# Kapitoshka.net
KiCad netlist of a schematic drawn in Altium Designer
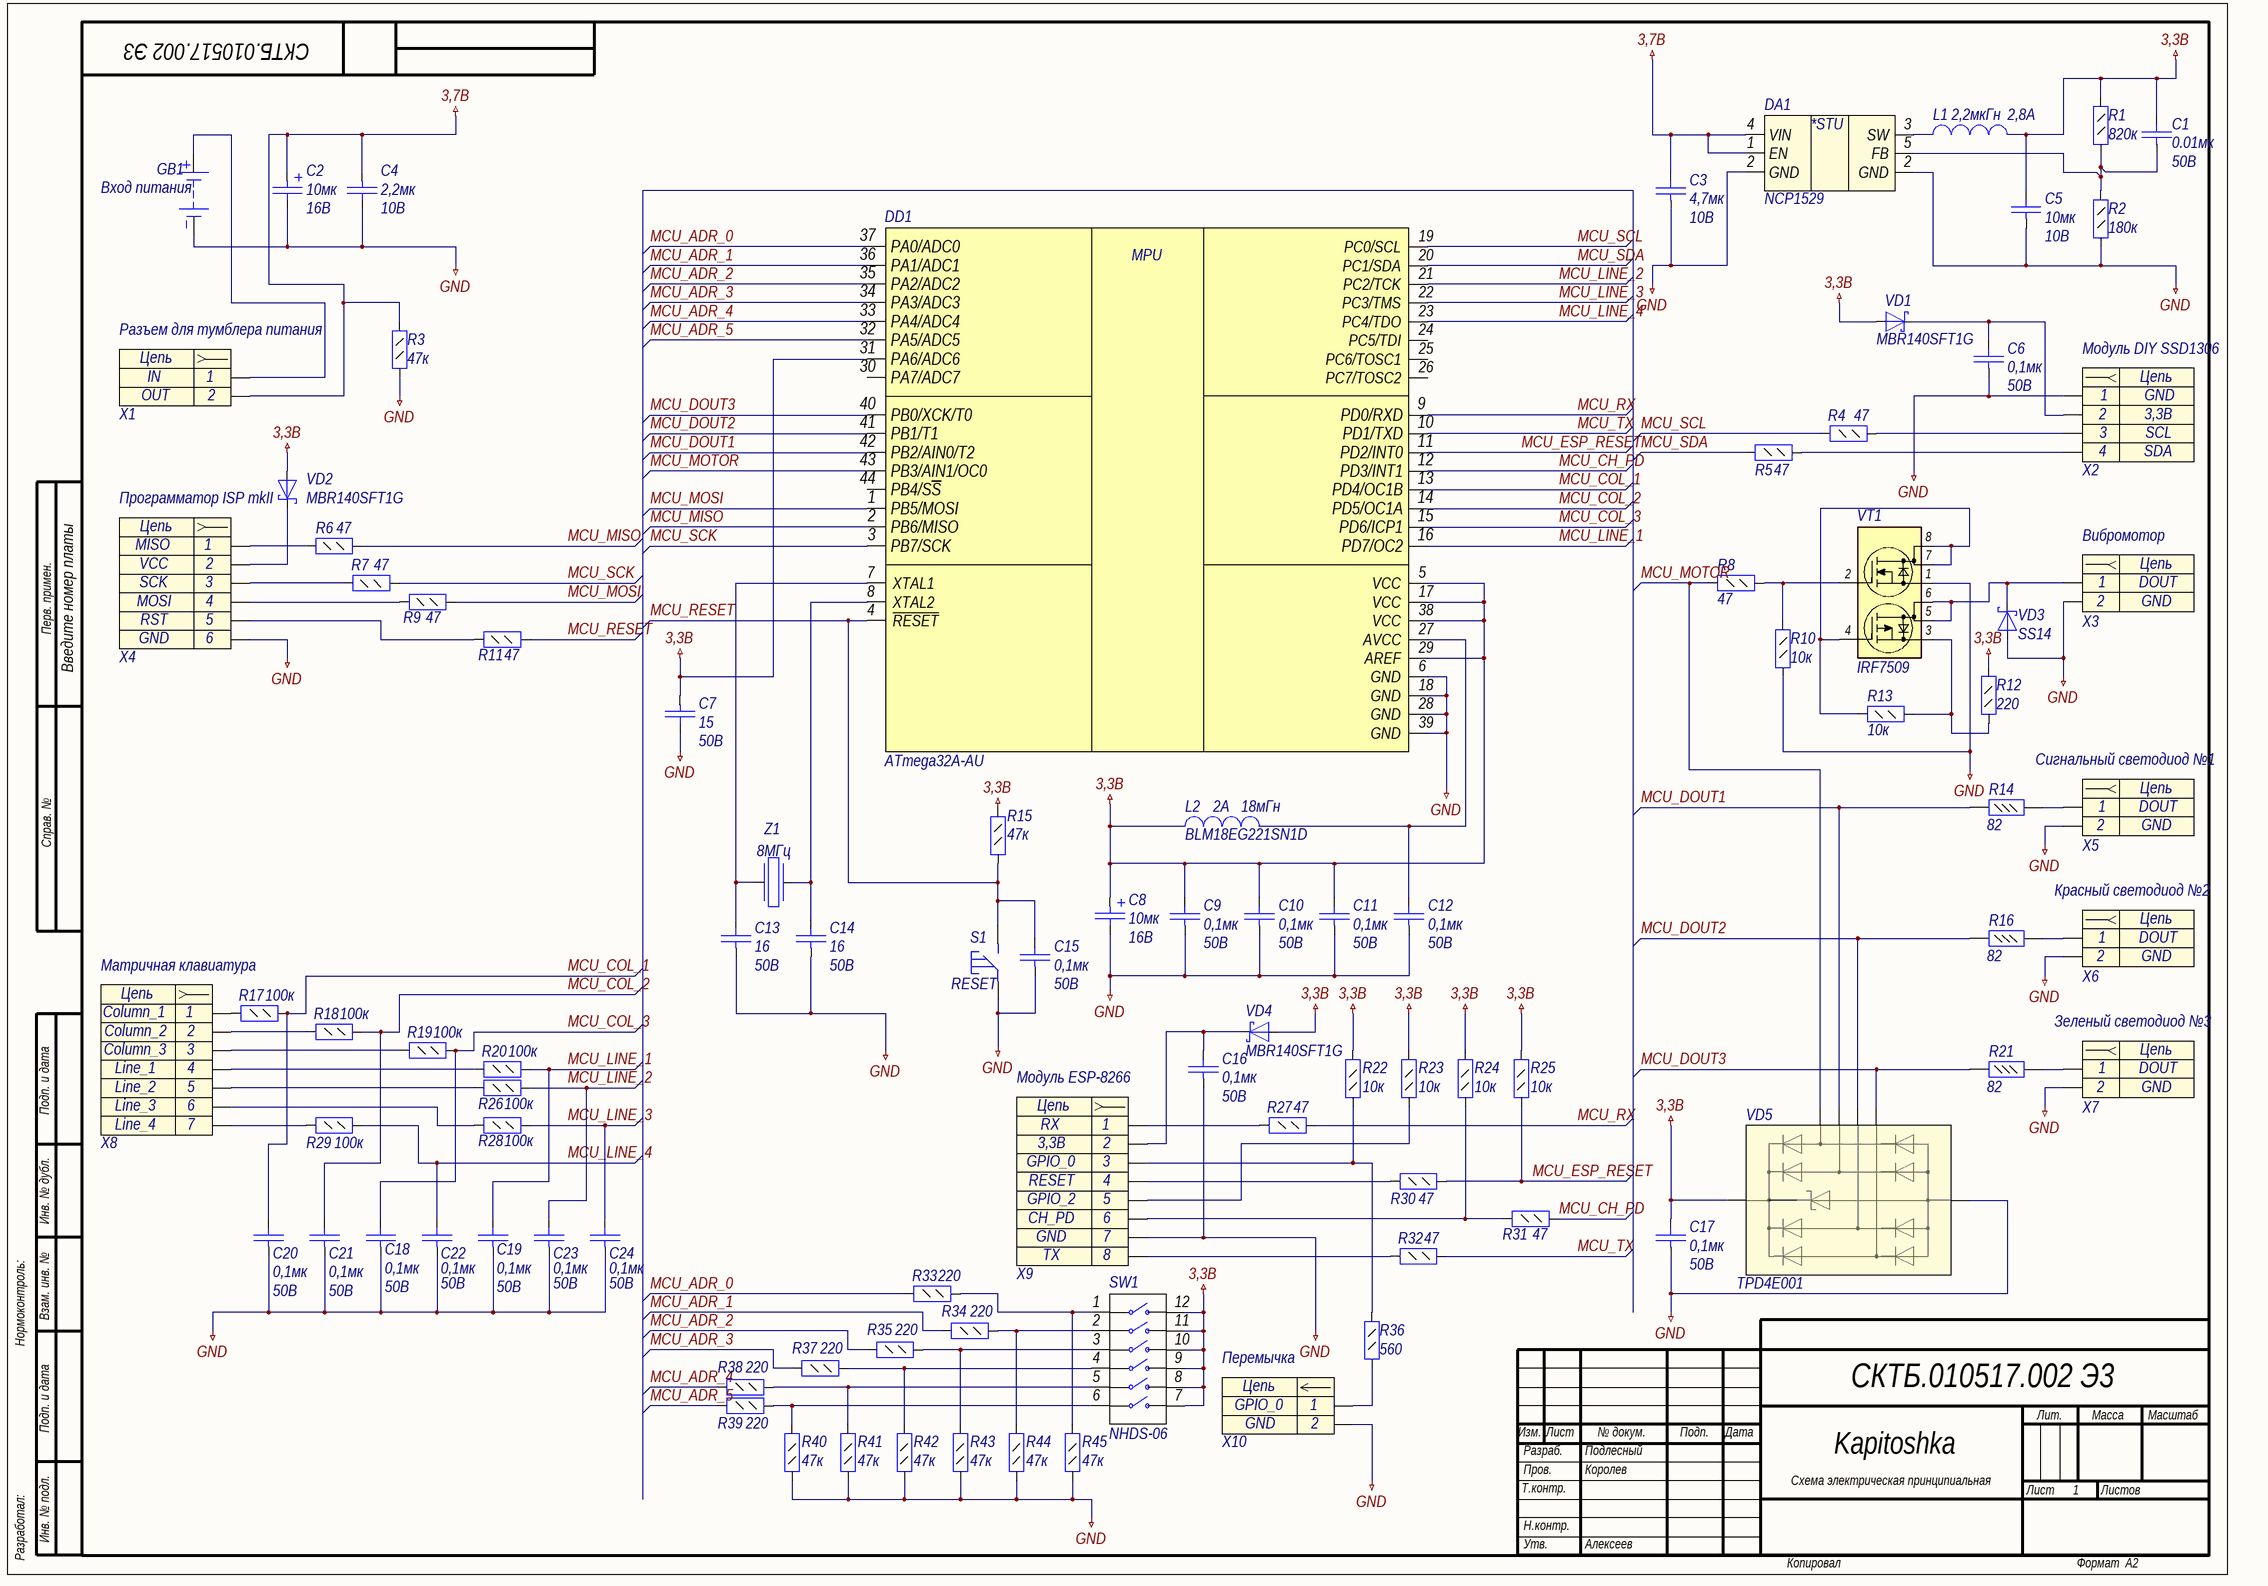
[diagram p0: Kapitoshka.SchDoc]

(export (version "E")
  (design (tool "Eeschema 10.0.6"))
  (components
    (comp (ref "C1")
      (value "0.01мк")
      (footprint "Kapitoshka:C0603")
      (description "Конденсатор")
      (fields (field (name "VOLTAGE") "50В"))
      (libsource (lib "Kapitoshka") (part "Capacitor"))
    )
    (comp (ref "C2")
      (value "10мк")
      (footprint "Kapitoshka:3216 Case-A")
      (description "Конденсатор полярный")
      (fields (field (name "VOLTAGE") "16В"))
      (libsource (lib "Kapitoshka") (part "Capacitor_pol"))
    )
    (comp (ref "C3")
      (value "4,7мк")
      (footprint "Kapitoshka:C0603")
      (description "Конденсатор")
      (fields (field (name "VOLTAGE") "10В"))
      (libsource (lib "Kapitoshka") (part "Capacitor"))
    )
    (comp (ref "C4")
      (value "2,2мк")
      (footprint "Kapitoshka:C0603")
      (description "Конденсатор")
      (fields (field (name "VOLTAGE") "10В"))
      (libsource (lib "Kapitoshka") (part "Capacitor"))
    )
    (comp (ref "C5")
      (value "10мк")
      (footprint "Kapitoshka:C0805")
      (description "Конденсатор")
      (fields (field (name "VOLTAGE") "10В"))
      (libsource (lib "Kapitoshka") (part "Capacitor"))
    )
    (comp (ref "C6")
      (value "0,1мк")
      (footprint "Kapitoshka:C0603")
      (description "Конденсатор")
      (fields (field (name "VOLTAGE") "50В"))
      (libsource (lib "Kapitoshka") (part "Capacitor"))
    )
    (comp (ref "C7")
      (value "15")
      (footprint "Kapitoshka:C0603")
      (description "Конденсатор")
      (fields (field (name "VOLTAGE") "50В"))
      (libsource (lib "Kapitoshka") (part "Capacitor"))
    )
    (comp (ref "C8")
      (value "10мк")
      (footprint "Kapitoshka:3216 Case-A")
      (description "Конденсатор полярный")
      (fields (field (name "VOLTAGE") "16В"))
      (libsource (lib "Kapitoshka") (part "Capacitor_pol"))
    )
    (comp (ref "C9")
      (value "0,1мк")
      (footprint "Kapitoshka:C0603")
      (description "Конденсатор")
      (fields (field (name "VOLTAGE") "50В"))
      (libsource (lib "Kapitoshka") (part "Capacitor"))
    )
    (comp (ref "C10")
      (value "0,1мк")
      (footprint "Kapitoshka:C0603")
      (description "Конденсатор")
      (fields (field (name "VOLTAGE") "50В"))
      (libsource (lib "Kapitoshka") (part "Capacitor"))
    )
    (comp (ref "C11")
      (value "0,1мк")
      (footprint "Kapitoshka:C0603")
      (description "Конденсатор")
      (fields (field (name "VOLTAGE") "50В"))
      (libsource (lib "Kapitoshka") (part "Capacitor"))
    )
    (comp (ref "C12")
      (value "0,1мк")
      (footprint "Kapitoshka:C0603")
      (description "Конденсатор")
      (fields (field (name "VOLTAGE") "50В"))
      (libsource (lib "Kapitoshka") (part "Capacitor"))
    )
    (comp (ref "C13")
      (value "16")
      (footprint "Kapitoshka:C0805")
      (description "Конденсатор")
      (fields (field (name "VOLTAGE") "50В"))
      (libsource (lib "Kapitoshka") (part "Capacitor"))
    )
    (comp (ref "C14")
      (value "16")
      (footprint "Kapitoshka:C0805")
      (description "Конденсатор")
      (fields (field (name "VOLTAGE") "50В"))
      (libsource (lib "Kapitoshka") (part "Capacitor"))
    )
    (comp (ref "C15")
      (value "0,1мк")
      (footprint "Kapitoshka:C0603")
      (description "Конденсатор")
      (fields (field (name "VOLTAGE") "50В"))
      (libsource (lib "Kapitoshka") (part "Capacitor"))
    )
    (comp (ref "C16")
      (value "0,1мк")
      (footprint "Kapitoshka:C0603")
      (description "Конденсатор")
      (fields (field (name "VOLTAGE") "50В"))
      (libsource (lib "Kapitoshka") (part "Capacitor"))
    )
    (comp (ref "C17")
      (value "0,1мк")
      (footprint "Kapitoshka:C0603")
      (description "Конденсатор")
      (fields (field (name "VOLTAGE") "50В"))
      (libsource (lib "Kapitoshka") (part "Capacitor"))
    )
    (comp (ref "C18")
      (value "0,1мк")
      (footprint "Kapitoshka:C0603")
      (description "Конденсатор")
      (fields (field (name "VOLTAGE") "50В"))
      (libsource (lib "Kapitoshka") (part "Capacitor"))
    )
    (comp (ref "C19")
      (value "0,1мк")
      (footprint "Kapitoshka:C0603")
      (description "Конденсатор")
      (fields (field (name "VOLTAGE") "50В"))
      (libsource (lib "Kapitoshka") (part "Capacitor"))
    )
    (comp (ref "C20")
      (value "0,1мк")
      (footprint "Kapitoshka:C0603")
      (description "Конденсатор")
      (fields (field (name "VOLTAGE") "50В"))
      (libsource (lib "Kapitoshka") (part "Capacitor"))
    )
    (comp (ref "C21")
      (value "0,1мк")
      (footprint "Kapitoshka:C0603")
      (description "Конденсатор")
      (fields (field (name "VOLTAGE") "50В"))
      (libsource (lib "Kapitoshka") (part "Capacitor"))
    )
    (comp (ref "C22")
      (value "0,1мк")
      (footprint "Kapitoshka:C0603")
      (description "Конденсатор")
      (fields (field (name "VOLTAGE") "50В"))
      (libsource (lib "Kapitoshka") (part "Capacitor"))
    )
    (comp (ref "C23")
      (value "0,1мк")
      (footprint "Kapitoshka:C0603")
      (description "Конденсатор")
      (fields (field (name "VOLTAGE") "50В"))
      (libsource (lib "Kapitoshka") (part "Capacitor"))
    )
    (comp (ref "C24")
      (value "0,1мк")
      (footprint "Kapitoshka:C0603")
      (description "Конденсатор")
      (fields (field (name "VOLTAGE") "50В"))
      (libsource (lib "Kapitoshka") (part "Capacitor"))
    )
    (comp (ref "DA1")
      (value "NCP1529")
      (footprint "Kapitoshka:TSOP-5")
      (description "Output Voltage Step-down  Converter")
      (libsource (lib "Kapitoshka") (part "NCP1529"))
    )
    (comp (ref "DD1")
      (value "ATmega32A-AU")
      (footprint "Kapitoshka:TQFP-44")
      (description "Микроконтроллер 44-pin")
      (fields (field (name "NAME") "ATmega32A-AU"))
      (libsource (lib "Kapitoshka") (part "ATmega32A-AU"))
    )
    (comp (ref "GB1")
      (value "Вход питания")
      (footprint "Kapitoshka:KLS5-818-D")
      (libsource (lib "Kapitoshka") (part "Battery compartment"))
    )
    (comp (ref "L1")
      (value "2,2мкГн")
      (footprint "Kapitoshka:SDR0604")
      (description "Катушка индуктивности")
      (fields (field (name "IMAX") "2,8А"))
      (libsource (lib "Kapitoshka") (part "Inductor"))
    )
    (comp (ref "L2")
      (value "18мГн")
      (footprint "Kapitoshka:L0603")
      (description "Катушка индуктивности")
      (fields (field (name "NAME") "BLM18EG221SN1D") (field (name "IMAX") "2А"))
      (libsource (lib "Kapitoshka") (part "Inductor"))
    )
    (comp (ref "R1")
      (value "820к")
      (footprint "Kapitoshka:R0603")
      (description "0.125Вт 0805 47 Ом, 1%, Чип резистор (SMD)")
      (libsource (lib "") (part "Resistor_0,125Вт_2"))
    )
    (comp (ref "R2")
      (value "180к")
      (footprint "Kapitoshka:R0603")
      (description "0.125Вт 0805 47 Ом, 1%, Чип резистор (SMD)")
      (libsource (lib "") (part "Resistor_0,125Вт_2"))
    )
    (comp (ref "R3")
      (value "47к")
      (footprint "Kapitoshka:R0603")
      (description "Резистор")
      (libsource (lib "") (part "Resistor_0,125Вт_2"))
    )
    (comp (ref "R4")
      (value "47")
      (footprint "Kapitoshka:R0603")
      (description "0.125Вт 0805 47 Ом, 1%, Чип резистор (SMD)")
      (libsource (lib "Stove_Light") (part "Resistor_0,125Вт"))
    )
    (comp (ref "R5")
      (value "47")
      (footprint "Kapitoshka:R0603")
      (description "0.125Вт 0805 47 Ом, 1%, Чип резистор (SMD)")
      (libsource (lib "Stove_Light") (part "Resistor_0,125Вт"))
    )
    (comp (ref "R6")
      (value "47")
      (footprint "Kapitoshka:R0603")
      (description "Резистор")
      (libsource (lib "") (part "Resistor_0,125Вт_1"))
    )
    (comp (ref "R7")
      (value "47")
      (footprint "Kapitoshka:R0603")
      (description "Резистор")
      (libsource (lib "") (part "Resistor_0,125Вт_1"))
    )
    (comp (ref "R8")
      (value "47")
      (footprint "Kapitoshka:R0603")
      (description "0.125Вт 0805 47 Ом, 1%, Чип резистор (SMD)")
      (libsource (lib "Stove_Light") (part "Resistor_0,125Вт"))
    )
    (comp (ref "R9")
      (value "47")
      (footprint "Kapitoshka:R0603")
      (description "Резистор")
      (libsource (lib "") (part "Resistor_0,125Вт_1"))
    )
    (comp (ref "R10")
      (value "10к")
      (footprint "Kapitoshka:R0603")
      (description "0.125Вт 0805 47 Ом, 1%, Чип резистор (SMD)")
      (libsource (lib "") (part "Resistor_0,125Вт_2"))
    )
    (comp (ref "R11")
      (value "47")
      (footprint "Kapitoshka:R0603")
      (description "Резистор")
      (libsource (lib "") (part "Resistor_0,125Вт_1"))
    )
    (comp (ref "R12")
      (value "220")
      (footprint "Kapitoshka:R0603")
      (description "0.125Вт 0805 47 Ом, 1%, Чип резистор (SMD)")
      (libsource (lib "") (part "Resistor_0,125Вт_3"))
    )
    (comp (ref "R13")
      (value "10к")
      (footprint "Kapitoshka:R0603")
      (description "0.125Вт 0805 10 кОм, 1%, Чип резистор (SMD)")
      (libsource (lib "") (part "Resistor_0,125Вт_1"))
    )
    (comp (ref "R14")
      (value "82")
      (footprint "Kapitoshka:R0603")
      (description "Резистор")
      (libsource (lib "Kapitoshka") (part "Resistor_0,05Вт"))
    )
    (comp (ref "R15")
      (value "47к")
      (footprint "Kapitoshka:R0603")
      (description "Резистор")
      (libsource (lib "") (part "Resistor_0,125Вт_2"))
    )
    (comp (ref "R16")
      (value "82")
      (footprint "Kapitoshka:R0603")
      (description "Резистор")
      (libsource (lib "Kapitoshka") (part "Resistor_0,05Вт"))
    )
    (comp (ref "R17")
      (value "100к")
      (footprint "Kapitoshka:R0603")
      (description "0.125Вт 0805 47 Ом, 1%, Чип резистор (SMD)")
      (libsource (lib "Stove_Light") (part "Resistor_0,125Вт"))
    )
    (comp (ref "R18")
      (value "100к")
      (footprint "Kapitoshka:R0603")
      (description "0.125Вт 0805 47 Ом, 1%, Чип резистор (SMD)")
      (libsource (lib "Stove_Light") (part "Resistor_0,125Вт"))
    )
    (comp (ref "R19")
      (value "100к")
      (footprint "Kapitoshka:R0603")
      (description "0.125Вт 0805 47 Ом, 1%, Чип резистор (SMD)")
      (libsource (lib "Stove_Light") (part "Resistor_0,125Вт"))
    )
    (comp (ref "R20")
      (value "100к")
      (footprint "Kapitoshka:R0603")
      (description "0.125Вт 0805 47 Ом, 1%, Чип резистор (SMD)")
      (libsource (lib "Stove_Light") (part "Resistor_0,125Вт"))
    )
    (comp (ref "R21")
      (value "82")
      (footprint "Kapitoshka:R0603")
      (description "Резистор")
      (libsource (lib "Kapitoshka") (part "Resistor_0,05Вт"))
    )
    (comp (ref "R22")
      (value "10к")
      (footprint "Kapitoshka:R0603")
      (description "Резистор")
      (libsource (lib "Kapitoshka") (part "Resistor_0,125Вт"))
    )
    (comp (ref "R23")
      (value "10к")
      (footprint "Kapitoshka:R0603")
      (description "Резистор")
      (libsource (lib "Kapitoshka") (part "Resistor_0,125Вт"))
    )
    (comp (ref "R24")
      (value "10к")
      (footprint "Kapitoshka:R0603")
      (description "Резистор")
      (libsource (lib "Kapitoshka") (part "Resistor_0,125Вт"))
    )
    (comp (ref "R25")
      (value "10к")
      (footprint "Kapitoshka:R0603")
      (description "Резистор")
      (libsource (lib "Kapitoshka") (part "Resistor_0,125Вт"))
    )
    (comp (ref "R26")
      (value "100к")
      (footprint "Kapitoshka:R0603")
      (description "0.125Вт 0805 47 Ом, 1%, Чип резистор (SMD)")
      (libsource (lib "Stove_Light") (part "Resistor_0,125Вт"))
    )
    (comp (ref "R27")
      (value "47")
      (footprint "Kapitoshka:R0603")
      (description "0.125Вт 0805 47 Ом, 1%, Чип резистор (SMD)")
      (libsource (lib "Stove_Light") (part "Resistor_0,125Вт"))
    )
    (comp (ref "R28")
      (value "100к")
      (footprint "Kapitoshka:R0603")
      (description "0.125Вт 0805 47 Ом, 1%, Чип резистор (SMD)")
      (libsource (lib "Stove_Light") (part "Resistor_0,125Вт"))
    )
    (comp (ref "R29")
      (value "100к")
      (footprint "Kapitoshka:R0603")
      (description "0.125Вт 0805 47 Ом, 1%, Чип резистор (SMD)")
      (libsource (lib "Stove_Light") (part "Resistor_0,125Вт"))
    )
    (comp (ref "R30")
      (value "47")
      (footprint "Kapitoshka:R0603")
      (description "0.125Вт 0805 47 Ом, 1%, Чип резистор (SMD)")
      (libsource (lib "Stove_Light") (part "Resistor_0,125Вт"))
    )
    (comp (ref "R31")
      (value "47")
      (footprint "Kapitoshka:R0603")
      (description "0.125Вт 0805 47 Ом, 1%, Чип резистор (SMD)")
      (libsource (lib "Stove_Light") (part "Resistor_0,125Вт"))
    )
    (comp (ref "R32")
      (value "47")
      (footprint "Kapitoshka:R0603")
      (description "0.125Вт 0805 47 Ом, 1%, Чип резистор (SMD)")
      (libsource (lib "Stove_Light") (part "Resistor_0,125Вт"))
    )
    (comp (ref "R33")
      (value "220")
      (footprint "Kapitoshka:R0603")
      (description "0.125Вт 0805 47 Ом, 1%, Чип резистор (SMD)")
      (libsource (lib "Stove_Light") (part "Resistor_0,125Вт"))
    )
    (comp (ref "R34")
      (value "220")
      (footprint "Kapitoshka:R0603")
      (description "0.125Вт 0805 47 Ом, 1%, Чип резистор (SMD)")
      (libsource (lib "Stove_Light") (part "Resistor_0,125Вт"))
    )
    (comp (ref "R35")
      (value "220")
      (footprint "Kapitoshka:R0603")
      (description "0.125Вт 0805 47 Ом, 1%, Чип резистор (SMD)")
      (libsource (lib "Stove_Light") (part "Resistor_0,125Вт"))
    )
    (comp (ref "R36")
      (value "560")
      (footprint "Kapitoshka:R0603")
      (description "0.125Вт 0805 47 Ом, 1%, Чип резистор (SMD)")
      (libsource (lib "") (part "Resistor_0,125Вт_2"))
    )
    (comp (ref "R37")
      (value "220")
      (footprint "Kapitoshka:R0603")
      (description "0.125Вт 0805 47 Ом, 1%, Чип резистор (SMD)")
      (libsource (lib "Stove_Light") (part "Resistor_0,125Вт"))
    )
    (comp (ref "R38")
      (value "220")
      (footprint "Kapitoshka:R0603")
      (description "0.125Вт 0805 47 Ом, 1%, Чип резистор (SMD)")
      (libsource (lib "Stove_Light") (part "Resistor_0,125Вт"))
    )
    (comp (ref "R39")
      (value "220")
      (footprint "Kapitoshka:R0603")
      (description "0.125Вт 0805 47 Ом, 1%, Чип резистор (SMD)")
      (libsource (lib "Stove_Light") (part "Resistor_0,125Вт"))
    )
    (comp (ref "R40")
      (value "47к")
      (footprint "Kapitoshka:R0603")
      (description "Резистор")
      (libsource (lib "Kapitoshka") (part "Resistor_0,125Вт"))
    )
    (comp (ref "R41")
      (value "47к")
      (footprint "Kapitoshka:R0603")
      (description "Резистор")
      (libsource (lib "Kapitoshka") (part "Resistor_0,125Вт"))
    )
    (comp (ref "R42")
      (value "47к")
      (footprint "Kapitoshka:R0603")
      (description "Резистор")
      (libsource (lib "Kapitoshka") (part "Resistor_0,125Вт"))
    )
    (comp (ref "R43")
      (value "47к")
      (footprint "Kapitoshka:R0603")
      (description "Резистор")
      (libsource (lib "Kapitoshka") (part "Resistor_0,125Вт"))
    )
    (comp (ref "R44")
      (value "47к")
      (footprint "Kapitoshka:R0603")
      (description "Резистор")
      (libsource (lib "Kapitoshka") (part "Resistor_0,125Вт"))
    )
    (comp (ref "R45")
      (value "47к")
      (footprint "Kapitoshka:R0603")
      (description "Резистор")
      (libsource (lib "Kapitoshka") (part "Resistor_0,125Вт"))
    )
    (comp (ref "S1")
      (value "RESET")
      (footprint "Kapitoshka:DTSM 32")
      (description "Кнопка")
      (fields (field (name "NAME") "RESET"))
      (libsource (lib "Kapitoshka") (part "Button_SMD"))
    )
    (comp (ref "SW1")
      (value "NHDS-06")
      (footprint "Kapitoshka:NHDS-06")
      (description "DIP переключатель")
      (libsource (lib "Kapitoshka") (part "DS1040-06"))
    )
    (comp (ref "VD1")
      (value "MBR140SFT1G")
      (footprint "Kapitoshka:SMA")
      (description "Диод Шоттки")
      (libsource (lib "Kapitoshka") (part "DiodeSchottky"))
    )
    (comp (ref "VD2")
      (value "MBR140SFT1G")
      (footprint "Kapitoshka:SMA")
      (description "Диод Шоттки")
      (libsource (lib "Kapitoshka") (part "DiodeSchottky"))
    )
    (comp (ref "VD3")
      (value "SS14")
      (footprint "Kapitoshka:SMA")
      (description "Диод Шоттки")
      (libsource (lib "Kapitoshka") (part "DiodeSchottky"))
    )
    (comp (ref "VD4")
      (value "MBR140SFT1G")
      (footprint "Kapitoshka:SMA")
      (description "Диод Шоттки")
      (libsource (lib "Kapitoshka") (part "DiodeSchottky"))
    )
    (comp (ref "VD5")
      (value "TPD4E001")
      (footprint "Kapitoshka:SOT23-6")
      (description "Диодная сборка")
      (fields (field (name "MANUFACTURER") "Texas Instruments"))
      (libsource (lib "Kapitoshka") (part "TPD4E001"))
    )
    (comp (ref "VT1")
      (value "IRF7509")
      (footprint "Kapitoshka:Micro8")
      (description "Комплементарная сборка МОП")
      (fields (field (name "NAME") "IRF7509"))
      (libsource (lib "Kapitoshka") (part "IRF7509"))
    )
    (comp (ref "X1")
      (value "Разъем для тумблера питания")
      (footprint "Kapitoshka:2HOLE")
      (description "Разъем - 2 конт. розетка")
      (libsource (lib "Kapitoshka") (part "Header_2_sct"))
    )
    (comp (ref "X2")
      (value "Модуль DIY SSD1306")
      (footprint "Kapitoshka:OLED SSD1306")
      (description "Разъем - 4 конт. розетка")
      (libsource (lib "Kapitoshka") (part "Header_4_sct"))
    )
    (comp (ref "X3")
      (value "Вибромотор")
      (footprint "Kapitoshka:2HOLE")
      (description "Разъем - 2 конт. розетка")
      (libsource (lib "") (part "Header_2_sct_1"))
    )
    (comp (ref "X4")
      (value "Программатор ISP mkII")
      (footprint "Kapitoshka:PLS2-6")
      (description "Разъем - 5 конт. розетка")
      (libsource (lib "Kapitoshka") (part "Header_6_sct"))
    )
    (comp (ref "X5")
      (value "Сигнальный светодиод №1")
      (footprint "Kapitoshka:2HOLE")
      (description "Разъем - 2 конт. розетка")
      (libsource (lib "") (part "Header_2_sct_1"))
    )
    (comp (ref "X6")
      (value "Красный светодиод №2")
      (footprint "Kapitoshka:2HOLE")
      (description "Разъем - 2 конт. розетка")
      (libsource (lib "") (part "Header_2_sct_1"))
    )
    (comp (ref "X7")
      (value "Зеленый светодиод №3")
      (footprint "Kapitoshka:2HOLE")
      (description "Разъем - 2 конт. розетка")
      (libsource (lib "") (part "Header_2_sct_1"))
    )
    (comp (ref "X8")
      (value "Матричная клавиатура")
      (footprint "Kapitoshka:7HOLE")
      (description "Разъем - 5 конт. розетка")
      (libsource (lib "Kapitoshka") (part "Header_7_sct_"))
    )
    (comp (ref "X9")
      (value "Модуль ESP-8266")
      (footprint "Kapitoshka:ESP8266")
      (description "Разъем - 5 конт. розетка")
      (libsource (lib "Kapitoshka") (part "Header_8_sct"))
    )
    (comp (ref "X10")
      (value "Перемычка")
      (footprint "Kapitoshka:PLS2-2")
      (description "Разъем - 2 конт. вилка")
      (libsource (lib "Kapitoshka") (part "Header_2_plg"))
    )
    (comp (ref "Z1")
      (value "8МГц")
      (footprint "Kapitoshka:QSMD3.2x5")
      (description "Кварцевый резонатор")
      (libsource (lib "Kapitoshka") (part "Crystal"))
    )
  )
  (nets
    (net (code "1") (name "/MCU_ADR_0") (class "Default")
      (node (ref "DD1") (pin "37") (pinfunction "PA0/ADC0_37") (pintype "passive"))
      (node (ref "R33") (pin "2") (pinfunction "5_2") (pintype "passive"))
    )
    (net (code "2") (name "/MCU_ADR_1") (class "Default")
      (node (ref "DD1") (pin "36") (pinfunction "PA1/ADC1_36") (pintype "passive"))
      (node (ref "R34") (pin "2") (pinfunction "5_2") (pintype "passive"))
    )
    (net (code "3") (name "/MCU_ADR_2") (class "Default")
      (node (ref "DD1") (pin "35") (pinfunction "PA2/ADC2_35") (pintype "passive"))
      (node (ref "R35") (pin "2") (pinfunction "5_2") (pintype "passive"))
    )
    (net (code "4") (name "/MCU_ADR_3") (class "Default")
      (node (ref "DD1") (pin "34") (pinfunction "PA3/ADC3_34") (pintype "passive"))
      (node (ref "R37") (pin "2") (pinfunction "5_2") (pintype "passive"))
    )
    (net (code "5") (name "/MCU_ADR_4") (class "Default")
      (node (ref "DD1") (pin "33") (pinfunction "PA4/ADC4_33") (pintype "passive"))
      (node (ref "R38") (pin "2") (pinfunction "5_2") (pintype "passive"))
    )
    (net (code "6") (name "/MCU_ADR_5") (class "Default")
      (node (ref "DD1") (pin "32") (pinfunction "PA5/ADC5_32") (pintype "passive"))
      (node (ref "R39") (pin "2") (pinfunction "5_2") (pintype "passive"))
    )
    (net (code "7") (name "/MCU_CH_PD") (class "Default")
      (node (ref "DD1") (pin "12") (pinfunction "PD3/INT1_12") (pintype "passive"))
      (node (ref "R31") (pin "1") (pinfunction "1_1") (pintype "passive"))
    )
    (net (code "8") (name "/MCU_COL_1") (class "Default")
      (node (ref "C20") (pin "2") (pinfunction "2_2") (pintype "passive"))
      (node (ref "DD1") (pin "13") (pinfunction "PD4/OC1B_13") (pintype "passive"))
      (node (ref "R17") (pin "1") (pinfunction "1_1") (pintype "passive"))
    )
    (net (code "9") (name "/MCU_COL_2") (class "Default")
      (node (ref "C21") (pin "2") (pinfunction "2_2") (pintype "passive"))
      (node (ref "DD1") (pin "14") (pinfunction "PD5/OC1A_14") (pintype "passive"))
      (node (ref "R18") (pin "1") (pinfunction "1_1") (pintype "passive"))
    )
    (net (code "10") (name "/MCU_COL_3") (class "Default")
      (node (ref "C18") (pin "2") (pinfunction "2_2") (pintype "passive"))
      (node (ref "DD1") (pin "15") (pinfunction "PD6/ICP1_15") (pintype "passive"))
      (node (ref "R19") (pin "1") (pinfunction "1_1") (pintype "passive"))
    )
    (net (code "11") (name "/MCU_DOUT1") (class "Default")
      (node (ref "DD1") (pin "42") (pinfunction "PB2/AIN0/T2_42") (pintype "passive"))
      (node (ref "R14") (pin "1") (pinfunction "1_1") (pintype "passive"))
      (node (ref "VD5") (pin "3") (pinfunction "IO2_3") (pintype "passive"))
    )
    (net (code "12") (name "/MCU_DOUT2") (class "Default")
      (node (ref "DD1") (pin "41") (pinfunction "PB1/T1_41") (pintype "passive"))
      (node (ref "R16") (pin "1") (pinfunction "1_1") (pintype "passive"))
      (node (ref "VD5") (pin "4") (pinfunction "IO3_4") (pintype "passive"))
    )
    (net (code "13") (name "/MCU_DOUT3") (class "Default")
      (node (ref "DD1") (pin "40") (pinfunction "PB0/XCK/T0_40") (pintype "passive"))
      (node (ref "R21") (pin "1") (pinfunction "1_1") (pintype "passive"))
      (node (ref "VD5") (pin "6") (pinfunction "IO4_6") (pintype "passive"))
    )
    (net (code "14") (name "/MCU_ESP_RESET") (class "Default")
      (node (ref "DD1") (pin "11") (pinfunction "PD2/INT0_11") (pintype "passive"))
      (node (ref "R25") (pin "1") (pinfunction "1_1") (pintype "passive"))
      (node (ref "R30") (pin "1") (pinfunction "1_1") (pintype "passive"))
    )
    (net (code "15") (name "/MCU_LINE_1") (class "Default")
      (node (ref "C19") (pin "2") (pinfunction "2_2") (pintype "passive"))
      (node (ref "DD1") (pin "16") (pinfunction "PD7/OC2_16") (pintype "passive"))
      (node (ref "R20") (pin "1") (pinfunction "1_1") (pintype "passive"))
    )
    (net (code "16") (name "/MCU_LINE_2") (class "Default")
      (node (ref "C23") (pin "2") (pinfunction "2_2") (pintype "passive"))
      (node (ref "DD1") (pin "21") (pinfunction "PC2/TCK_21") (pintype "passive"))
      (node (ref "R26") (pin "1") (pinfunction "1_1") (pintype "passive"))
    )
    (net (code "17") (name "/MCU_LINE_3") (class "Default")
      (node (ref "C24") (pin "2") (pinfunction "2_2") (pintype "passive"))
      (node (ref "DD1") (pin "22") (pinfunction "PC3/TMS_22") (pintype "passive"))
      (node (ref "R28") (pin "1") (pinfunction "1_1") (pintype "passive"))
    )
    (net (code "18") (name "/MCU_LINE_4") (class "Default")
      (node (ref "C22") (pin "2") (pinfunction "2_2") (pintype "passive"))
      (node (ref "DD1") (pin "23") (pinfunction "PC4/TDO_23") (pintype "passive"))
      (node (ref "R29") (pin "1") (pinfunction "1_1") (pintype "passive"))
    )
    (net (code "19") (name "/MCU_MISO") (class "Default")
      (node (ref "DD1") (pin "2") (pinfunction "PB6/MISO_2") (pintype "passive"))
      (node (ref "R6") (pin "2") (pinfunction "5_2") (pintype "passive"))
    )
    (net (code "20") (name "/MCU_MOSI") (class "Default")
      (node (ref "DD1") (pin "1") (pinfunction "PB5/MOSI_1") (pintype "passive"))
      (node (ref "R9") (pin "2") (pinfunction "5_2") (pintype "passive"))
    )
    (net (code "21") (name "/MCU_MOTOR") (class "Default")
      (node (ref "DD1") (pin "43") (pinfunction "PB3/AIN1/OC0_43") (pintype "passive"))
      (node (ref "R8") (pin "2") (pinfunction "5_2") (pintype "passive"))
      (node (ref "VD5") (pin "1") (pinfunction "IO1_1") (pintype "passive"))
    )
    (net (code "22") (name "/MCU_RESET") (class "Default")
      (node (ref "C15") (pin "2") (pinfunction "2_2") (pintype "passive"))
      (node (ref "DD1") (pin "4") (pinfunction "~{RESET}_4") (pintype "passive"))
      (node (ref "R11") (pin "2") (pinfunction "5_2") (pintype "passive"))
      (node (ref "R15") (pin "2") (pinfunction "5_2") (pintype "passive"))
      (node (ref "S1") (pin "3") (pinfunction "3_3") (pintype "passive"))
    )
    (net (code "23") (name "/MCU_RX") (class "Default")
      (node (ref "DD1") (pin "9") (pinfunction "PD0/RXD_9") (pintype "passive"))
      (node (ref "R27") (pin "1") (pinfunction "1_1") (pintype "passive"))
    )
    (net (code "24") (name "/MCU_SCK") (class "Default")
      (node (ref "DD1") (pin "3") (pinfunction "PB7/SCK_3") (pintype "passive"))
      (node (ref "R7") (pin "2") (pinfunction "5_2") (pintype "passive"))
    )
    (net (code "25") (name "/MCU_SCL") (class "Default")
      (node (ref "DD1") (pin "19") (pinfunction "PC0/SCL_19") (pintype "passive"))
      (node (ref "R4") (pin "2") (pinfunction "5_2") (pintype "passive"))
    )
    (net (code "26") (name "/MCU_SDA") (class "Default")
      (node (ref "DD1") (pin "20") (pinfunction "PC1/SDA_20") (pintype "passive"))
      (node (ref "R5") (pin "2") (pinfunction "5_2") (pintype "passive"))
    )
    (net (code "27") (name "/MCU_TX") (class "Default")
      (node (ref "DD1") (pin "10") (pinfunction "PD1/TXD_10") (pintype "passive"))
      (node (ref "R32") (pin "1") (pinfunction "1_1") (pintype "passive"))
    )
    (net (code "28") (name "3,3В") (class "Default")
      (node (ref "C1") (pin "2") (pinfunction "2_2") (pintype "passive"))
      (node (ref "C10") (pin "2") (pinfunction "2_2") (pintype "passive"))
      (node (ref "C11") (pin "2") (pinfunction "2_2") (pintype "passive"))
      (node (ref "C17") (pin "2") (pinfunction "2_2") (pintype "passive"))
      (node (ref "C5") (pin "2") (pinfunction "2_2") (pintype "passive"))
      (node (ref "C7") (pin "1") (pinfunction "1_1") (pintype "passive"))
      (node (ref "C8") (pin "1") (pinfunction "1_1") (pintype "passive"))
      (node (ref "C9") (pin "2") (pinfunction "2_2") (pintype "passive"))
      (node (ref "DD1") (pin "17") (pinfunction "VCC_17") (pintype "passive"))
      (node (ref "DD1") (pin "29") (pinfunction "AREF_29") (pintype "passive"))
      (node (ref "DD1") (pin "31") (pinfunction "PA6/ADC6_31") (pintype "passive"))
      (node (ref "DD1") (pin "38") (pinfunction "VCC_38") (pintype "passive"))
      (node (ref "DD1") (pin "5") (pinfunction "VCC_5") (pintype "passive"))
      (node (ref "L1") (pin "2") (pinfunction "2_2") (pintype "passive"))
      (node (ref "L2") (pin "1") (pinfunction "1_1") (pintype "passive"))
      (node (ref "R1") (pin "1") (pinfunction "1_1") (pintype "passive"))
      (node (ref "R12") (pin "2") (pinfunction "5_2") (pintype "passive"))
      (node (ref "R15") (pin "1") (pinfunction "1_1") (pintype "passive"))
      (node (ref "R22") (pin "2") (pinfunction "5_2") (pintype "passive"))
      (node (ref "R23") (pin "2") (pinfunction "5_2") (pintype "passive"))
      (node (ref "R24") (pin "2") (pinfunction "5_2") (pintype "passive"))
      (node (ref "R25") (pin "2") (pinfunction "5_2") (pintype "passive"))
      (node (ref "SW1") (pin "10") (pintype "passive"))
      (node (ref "SW1") (pin "11") (pintype "passive"))
      (node (ref "SW1") (pin "12") (pintype "passive"))
      (node (ref "SW1") (pin "7") (pintype "passive"))
      (node (ref "SW1") (pin "8") (pintype "passive"))
      (node (ref "SW1") (pin "9") (pintype "passive"))
      (node (ref "VD1") (pin "2") (pinfunction "A_2") (pintype "passive"))
      (node (ref "VD2") (pin "2") (pinfunction "A_2") (pintype "passive"))
      (node (ref "VD4") (pin "2") (pinfunction "A_2") (pintype "passive"))
      (node (ref "VD5") (pin "5") (pinfunction "VCC_5") (pintype "passive"))
    )
    (net (code "29") (name "3,7В") (class "Default")
      (node (ref "C2") (pin "1") (pinfunction "1_1") (pintype "passive"))
      (node (ref "C3") (pin "2") (pinfunction "2_2") (pintype "passive"))
      (node (ref "C4") (pin "1") (pinfunction "1_1") (pintype "passive"))
      (node (ref "DA1") (pin "1") (pinfunction "EN_1") (pintype "power_in"))
      (node (ref "DA1") (pin "4") (pinfunction "VIN_4") (pintype "power_in"))
      (node (ref "R3") (pin "1") (pinfunction "1_1") (pintype "passive"))
      (node (ref "X1") (pin "2") (pinfunction "2_2") (pintype "passive"))
    )
    (net (code "30") (name "GND") (class "Default")
      (node (ref "C10") (pin "1") (pinfunction "1_1") (pintype "passive"))
      (node (ref "C11") (pin "1") (pinfunction "1_1") (pintype "passive"))
      (node (ref "C12") (pin "1") (pinfunction "1_1") (pintype "passive"))
      (node (ref "C13") (pin "1") (pinfunction "1_1") (pintype "passive"))
      (node (ref "C14") (pin "1") (pinfunction "1_1") (pintype "passive"))
      (node (ref "C15") (pin "1") (pinfunction "1_1") (pintype "passive"))
      (node (ref "C16") (pin "1") (pinfunction "1_1") (pintype "passive"))
      (node (ref "C17") (pin "1") (pinfunction "1_1") (pintype "passive"))
      (node (ref "C18") (pin "1") (pinfunction "1_1") (pintype "passive"))
      (node (ref "C19") (pin "1") (pinfunction "1_1") (pintype "passive"))
      (node (ref "C2") (pin "2") (pinfunction "2_2") (pintype "passive"))
      (node (ref "C20") (pin "1") (pinfunction "1_1") (pintype "passive"))
      (node (ref "C21") (pin "1") (pinfunction "1_1") (pintype "passive"))
      (node (ref "C22") (pin "1") (pinfunction "1_1") (pintype "passive"))
      (node (ref "C23") (pin "1") (pinfunction "1_1") (pintype "passive"))
      (node (ref "C24") (pin "1") (pinfunction "1_1") (pintype "passive"))
      (node (ref "C3") (pin "1") (pinfunction "1_1") (pintype "passive"))
      (node (ref "C4") (pin "2") (pinfunction "2_2") (pintype "passive"))
      (node (ref "C5") (pin "1") (pinfunction "1_1") (pintype "passive"))
      (node (ref "C6") (pin "1") (pinfunction "1_1") (pintype "passive"))
      (node (ref "C7") (pin "2") (pinfunction "2_2") (pintype "passive"))
      (node (ref "C8") (pin "2") (pinfunction "2_2") (pintype "passive"))
      (node (ref "C9") (pin "1") (pinfunction "1_1") (pintype "passive"))
      (node (ref "DA1") (pin "2") (pinfunction "GND_2") (pintype "power_in"))
      (node (ref "DD1") (pin "18") (pinfunction "GND_18") (pintype "passive"))
      (node (ref "DD1") (pin "28") (pinfunction "GND_28") (pintype "passive"))
      (node (ref "DD1") (pin "39") (pinfunction "GND_39") (pintype "passive"))
      (node (ref "DD1") (pin "6") (pinfunction "GND_6") (pintype "passive"))
      (node (ref "GB1") (pin "2") (pinfunction "2_2") (pintype "passive"))
      (node (ref "R10") (pin "2") (pinfunction "5_2") (pintype "passive"))
      (node (ref "R2") (pin "2") (pinfunction "5_2") (pintype "passive"))
      (node (ref "R3") (pin "2") (pinfunction "5_2") (pintype "passive"))
      (node (ref "R40") (pin "1") (pinfunction "1_1") (pintype "passive"))
      (node (ref "R41") (pin "1") (pinfunction "1_1") (pintype "passive"))
      (node (ref "R42") (pin "1") (pinfunction "1_1") (pintype "passive"))
      (node (ref "R43") (pin "1") (pinfunction "1_1") (pintype "passive"))
      (node (ref "R44") (pin "1") (pinfunction "1_1") (pintype "passive"))
      (node (ref "R45") (pin "1") (pinfunction "1_1") (pintype "passive"))
      (node (ref "S1") (pin "1") (pinfunction "1_1") (pintype "passive"))
      (node (ref "VD3") (pin "2") (pinfunction "A_2") (pintype "passive"))
      (node (ref "VD5") (pin "2") (pinfunction "GND_2") (pintype "passive"))
      (node (ref "VT1") (pin "1") (pinfunction "S1_1") (pintype "passive"))
      (node (ref "X10") (pin "2") (pinfunction "2_2") (pintype "passive"))
      (node (ref "X2") (pin "1") (pinfunction "1_1") (pintype "passive"))
      (node (ref "X3") (pin "2") (pinfunction "2_2") (pintype "passive"))
      (node (ref "X4") (pin "6") (pinfunction "6_6") (pintype "passive"))
      (node (ref "X5") (pin "2") (pinfunction "2_2") (pintype "passive"))
      (node (ref "X6") (pin "2") (pinfunction "2_2") (pintype "passive"))
      (node (ref "X7") (pin "2") (pinfunction "2_2") (pintype "passive"))
      (node (ref "X9") (pin "7") (pinfunction "7_7") (pintype "passive"))
    )
    (net (code "31") (name "Net-(DA1-FB)") (class "Default")
      (node (ref "C1") (pin "1") (pinfunction "1_1") (pintype "passive"))
      (node (ref "DA1") (pin "5") (pinfunction "FB_5") (pintype "power_in"))
      (node (ref "R1") (pin "2") (pinfunction "5_2") (pintype "passive"))
      (node (ref "R2") (pin "1") (pinfunction "1_1") (pintype "passive"))
    )
    (net (code "32") (name "Net-(DA1-SW)") (class "Default")
      (node (ref "DA1") (pin "3") (pinfunction "SW_3") (pintype "power_in"))
      (node (ref "L1") (pin "1") (pinfunction "1_1") (pintype "passive"))
    )
    (net (code "33") (name "Net-(DD1-AVCC)") (class "Default")
      (node (ref "C12") (pin "2") (pinfunction "2_2") (pintype "passive"))
      (node (ref "DD1") (pin "27") (pinfunction "AVCC_27") (pintype "passive"))
      (node (ref "L2") (pin "2") (pinfunction "2_2") (pintype "passive"))
    )
    (net (code "34") (name "Net-(DD1-XTAL1)") (class "Default")
      (node (ref "C13") (pin "2") (pinfunction "2_2") (pintype "passive"))
      (node (ref "DD1") (pin "7") (pinfunction "XTAL1_7") (pintype "passive"))
      (node (ref "Z1") (pin "2") (pinfunction "2_2") (pintype "passive"))
    )
    (net (code "35") (name "Net-(DD1-XTAL2)") (class "Default")
      (node (ref "C14") (pin "2") (pinfunction "2_2") (pintype "passive"))
      (node (ref "DD1") (pin "8") (pinfunction "XTAL2_8") (pintype "passive"))
      (node (ref "Z1") (pin "1") (pinfunction "1_1") (pintype "passive"))
    )
    (net (code "36") (name "Net-(GB1-Pad1)") (class "Default")
      (node (ref "GB1") (pin "1") (pinfunction "1_1") (pintype "passive"))
      (node (ref "X1") (pin "1") (pinfunction "1_1") (pintype "passive"))
    )
    (net (code "37") (name "Net-(R4-Pad1)") (class "Default")
      (node (ref "R4") (pin "1") (pinfunction "1_1") (pintype "passive"))
      (node (ref "X2") (pin "3") (pinfunction "3_3") (pintype "passive"))
    )
    (net (code "38") (name "Net-(R5-Pad1)") (class "Default")
      (node (ref "R5") (pin "1") (pinfunction "1_1") (pintype "passive"))
      (node (ref "X2") (pin "4") (pinfunction "4_4") (pintype "passive"))
    )
    (net (code "39") (name "Net-(R6-Pad1)") (class "Default")
      (node (ref "R6") (pin "1") (pinfunction "1_1") (pintype "passive"))
      (node (ref "X4") (pin "1") (pinfunction "1_1") (pintype "passive"))
    )
    (net (code "40") (name "Net-(R7-Pad1)") (class "Default")
      (node (ref "R7") (pin "1") (pinfunction "1_1") (pintype "passive"))
      (node (ref "X4") (pin "3") (pinfunction "3_3") (pintype "passive"))
    )
    (net (code "41") (name "Net-(R9-Pad1)") (class "Default")
      (node (ref "R9") (pin "1") (pinfunction "1_1") (pintype "passive"))
      (node (ref "X4") (pin "4") (pinfunction "4_4") (pintype "passive"))
    )
    (net (code "42") (name "Net-(R11-Pad1)") (class "Default")
      (node (ref "R11") (pin "1") (pinfunction "1_1") (pintype "passive"))
      (node (ref "X4") (pin "5") (pinfunction "5_5") (pintype "passive"))
    )
    (net (code "43") (name "Net-(R13-5)") (class "Default")
      (node (ref "R12") (pin "1") (pinfunction "1_1") (pintype "passive"))
      (node (ref "R13") (pin "2") (pinfunction "5_2") (pintype "passive"))
      (node (ref "VT1") (pin "3") (pinfunction "S2_3") (pintype "passive"))
    )
    (net (code "44") (name "Net-(R14-Pad2)") (class "Default")
      (node (ref "R14") (pin "2") (pinfunction "2_2") (pintype "passive"))
      (node (ref "X5") (pin "1") (pinfunction "1_1") (pintype "passive"))
    )
    (net (code "45") (name "Net-(R16-Pad2)") (class "Default")
      (node (ref "R16") (pin "2") (pinfunction "2_2") (pintype "passive"))
      (node (ref "X6") (pin "1") (pinfunction "1_1") (pintype "passive"))
    )
    (net (code "46") (name "Net-(R17-5)") (class "Default")
      (node (ref "R17") (pin "2") (pinfunction "5_2") (pintype "passive"))
      (node (ref "X8") (pin "1") (pinfunction "1_1") (pintype "passive"))
    )
    (net (code "47") (name "Net-(R18-5)") (class "Default")
      (node (ref "R18") (pin "2") (pinfunction "5_2") (pintype "passive"))
      (node (ref "X8") (pin "2") (pinfunction "2_2") (pintype "passive"))
    )
    (net (code "48") (name "Net-(R19-5)") (class "Default")
      (node (ref "R19") (pin "2") (pinfunction "5_2") (pintype "passive"))
      (node (ref "X8") (pin "3") (pinfunction "3_3") (pintype "passive"))
    )
    (net (code "49") (name "Net-(R20-5)") (class "Default")
      (node (ref "R20") (pin "2") (pinfunction "5_2") (pintype "passive"))
      (node (ref "X8") (pin "4") (pinfunction "4_4") (pintype "passive"))
    )
    (net (code "50") (name "Net-(R21-Pad2)") (class "Default")
      (node (ref "R21") (pin "2") (pinfunction "2_2") (pintype "passive"))
      (node (ref "X7") (pin "1") (pinfunction "1_1") (pintype "passive"))
    )
    (net (code "51") (name "Net-(R22-Pad1)") (class "Default")
      (node (ref "R22") (pin "1") (pinfunction "1_1") (pintype "passive"))
      (node (ref "R36") (pin "1") (pinfunction "1_1") (pintype "passive"))
      (node (ref "X9") (pin "3") (pinfunction "3_3") (pintype "passive"))
    )
    (net (code "52") (name "Net-(R23-Pad1)") (class "Default")
      (node (ref "R23") (pin "1") (pinfunction "1_1") (pintype "passive"))
      (node (ref "X9") (pin "5") (pinfunction "5_5") (pintype "passive"))
    )
    (net (code "53") (name "Net-(R26-5)") (class "Default")
      (node (ref "R26") (pin "2") (pinfunction "5_2") (pintype "passive"))
      (node (ref "X8") (pin "5") (pinfunction "5_5") (pintype "passive"))
    )
    (net (code "54") (name "Net-(R27-5)") (class "Default")
      (node (ref "R27") (pin "2") (pinfunction "5_2") (pintype "passive"))
      (node (ref "X9") (pin "1") (pinfunction "1_1") (pintype "passive"))
    )
    (net (code "55") (name "Net-(R28-5)") (class "Default")
      (node (ref "R28") (pin "2") (pinfunction "5_2") (pintype "passive"))
      (node (ref "X8") (pin "6") (pinfunction "6_6") (pintype "passive"))
    )
    (net (code "56") (name "Net-(R29-5)") (class "Default")
      (node (ref "R29") (pin "2") (pinfunction "5_2") (pintype "passive"))
      (node (ref "X8") (pin "7") (pinfunction "7_7") (pintype "passive"))
    )
    (net (code "57") (name "Net-(R30-5)") (class "Default")
      (node (ref "R30") (pin "2") (pinfunction "5_2") (pintype "passive"))
      (node (ref "X9") (pin "4") (pinfunction "4_4") (pintype "passive"))
    )
    (net (code "58") (name "Net-(R31-5)") (class "Default")
      (node (ref "R24") (pin "1") (pinfunction "1_1") (pintype "passive"))
      (node (ref "R31") (pin "2") (pinfunction "5_2") (pintype "passive"))
      (node (ref "X9") (pin "6") (pinfunction "6_6") (pintype "passive"))
    )
    (net (code "59") (name "Net-(R32-5)") (class "Default")
      (node (ref "R32") (pin "2") (pinfunction "5_2") (pintype "passive"))
      (node (ref "X9") (pin "8") (pinfunction "8_8") (pintype "passive"))
    )
    (net (code "60") (name "Net-(R36-5)") (class "Default")
      (node (ref "R36") (pin "2") (pinfunction "5_2") (pintype "passive"))
      (node (ref "X10") (pin "1") (pinfunction "1_1") (pintype "passive"))
    )
    (net (code "61") (name "Net-(R40-5)") (class "Default")
      (node (ref "R39") (pin "1") (pinfunction "1_1") (pintype "passive"))
      (node (ref "R40") (pin "2") (pinfunction "5_2") (pintype "passive"))
      (node (ref "SW1") (pin "6") (pintype "passive"))
    )
    (net (code "62") (name "Net-(R41-5)") (class "Default")
      (node (ref "R38") (pin "1") (pinfunction "1_1") (pintype "passive"))
      (node (ref "R41") (pin "2") (pinfunction "5_2") (pintype "passive"))
      (node (ref "SW1") (pin "5") (pintype "passive"))
    )
    (net (code "63") (name "Net-(R42-5)") (class "Default")
      (node (ref "R37") (pin "1") (pinfunction "1_1") (pintype "passive"))
      (node (ref "R42") (pin "2") (pinfunction "5_2") (pintype "passive"))
      (node (ref "SW1") (pin "4") (pintype "passive"))
    )
    (net (code "64") (name "Net-(R43-5)") (class "Default")
      (node (ref "R35") (pin "1") (pinfunction "1_1") (pintype "passive"))
      (node (ref "R43") (pin "2") (pinfunction "5_2") (pintype "passive"))
      (node (ref "SW1") (pin "3") (pintype "passive"))
    )
    (net (code "65") (name "Net-(R44-5)") (class "Default")
      (node (ref "R34") (pin "1") (pinfunction "1_1") (pintype "passive"))
      (node (ref "R44") (pin "2") (pinfunction "5_2") (pintype "passive"))
      (node (ref "SW1") (pin "2") (pintype "passive"))
    )
    (net (code "66") (name "Net-(R45-5)") (class "Default")
      (node (ref "R33") (pin "1") (pinfunction "1_1") (pintype "passive"))
      (node (ref "R45") (pin "2") (pinfunction "5_2") (pintype "passive"))
      (node (ref "SW1") (pin "1") (pintype "passive"))
    )
    (net (code "67") (name "Net-(VD1-K)") (class "Default")
      (node (ref "C6") (pin "2") (pinfunction "2_2") (pintype "passive"))
      (node (ref "VD1") (pin "1") (pinfunction "K_1") (pintype "passive"))
      (node (ref "X2") (pin "2") (pinfunction "2_2") (pintype "passive"))
    )
    (net (code "68") (name "Net-(VD2-K)") (class "Default")
      (node (ref "VD2") (pin "1") (pinfunction "K_1") (pintype "passive"))
      (node (ref "X4") (pin "2") (pinfunction "2_2") (pintype "passive"))
    )
    (net (code "69") (name "Net-(VD3-K)") (class "Default")
      (node (ref "VD3") (pin "1") (pinfunction "K_1") (pintype "passive"))
      (node (ref "VT1") (pin "5") (pinfunction "D2_5") (pintype "passive"))
      (node (ref "VT1") (pin "6") (pinfunction "D2_6") (pintype "passive"))
      (node (ref "X3") (pin "1") (pinfunction "1_1") (pintype "passive"))
    )
    (net (code "70") (name "Net-(VD4-K)") (class "Default")
      (node (ref "C16") (pin "2") (pinfunction "2_2") (pintype "passive"))
      (node (ref "VD4") (pin "1") (pinfunction "K_1") (pintype "passive"))
      (node (ref "X9") (pin "2") (pinfunction "2_2") (pintype "passive"))
    )
    (net (code "71") (name "Net-(VT1-G1)") (class "Default")
      (node (ref "R10") (pin "1") (pinfunction "1_1") (pintype "passive"))
      (node (ref "R8") (pin "1") (pinfunction "1_1") (pintype "passive"))
      (node (ref "VT1") (pin "2") (pinfunction "G1_2") (pintype "passive"))
    )
    (net (code "72") (name "Net-(VT1-G2)") (class "Default")
      (node (ref "R13") (pin "1") (pinfunction "1_1") (pintype "passive"))
      (node (ref "VT1") (pin "4") (pinfunction "G2_4") (pintype "passive"))
      (node (ref "VT1") (pin "7") (pinfunction "D1_7") (pintype "passive"))
      (node (ref "VT1") (pin "8") (pinfunction "D1_8") (pintype "passive"))
    )
    (net (code "73") (name "unconnected-(DD1-PA7{slash}ADC7-Pad30)") (class "Default")
      (node (ref "DD1") (pin "30") (pinfunction "PA7/ADC7_30") (pintype "passive"))
    )
    (net (code "74") (name "unconnected-(DD1-PB4{slash}S~{S}-Pad44)") (class "Default")
      (node (ref "DD1") (pin "44") (pinfunction "PB4/S~{S}_44") (pintype "passive"))
    )
    (net (code "75") (name "unconnected-(DD1-PC5{slash}TDI-Pad24)") (class "Default")
      (node (ref "DD1") (pin "24") (pinfunction "PC5/TDI_24") (pintype "passive"))
    )
    (net (code "76") (name "unconnected-(DD1-PC6{slash}TOSC1-Pad25)") (class "Default")
      (node (ref "DD1") (pin "25") (pinfunction "PC6/TOSC1_25") (pintype "passive"))
    )
    (net (code "77") (name "unconnected-(DD1-PC7{slash}TOSC2-Pad26)") (class "Default")
      (node (ref "DD1") (pin "26") (pinfunction "PC7/TOSC2_26") (pintype "passive"))
    )
  )
)
